# Power_Supply.net
KiCad netlist of a schematic drawn in Altium Designer
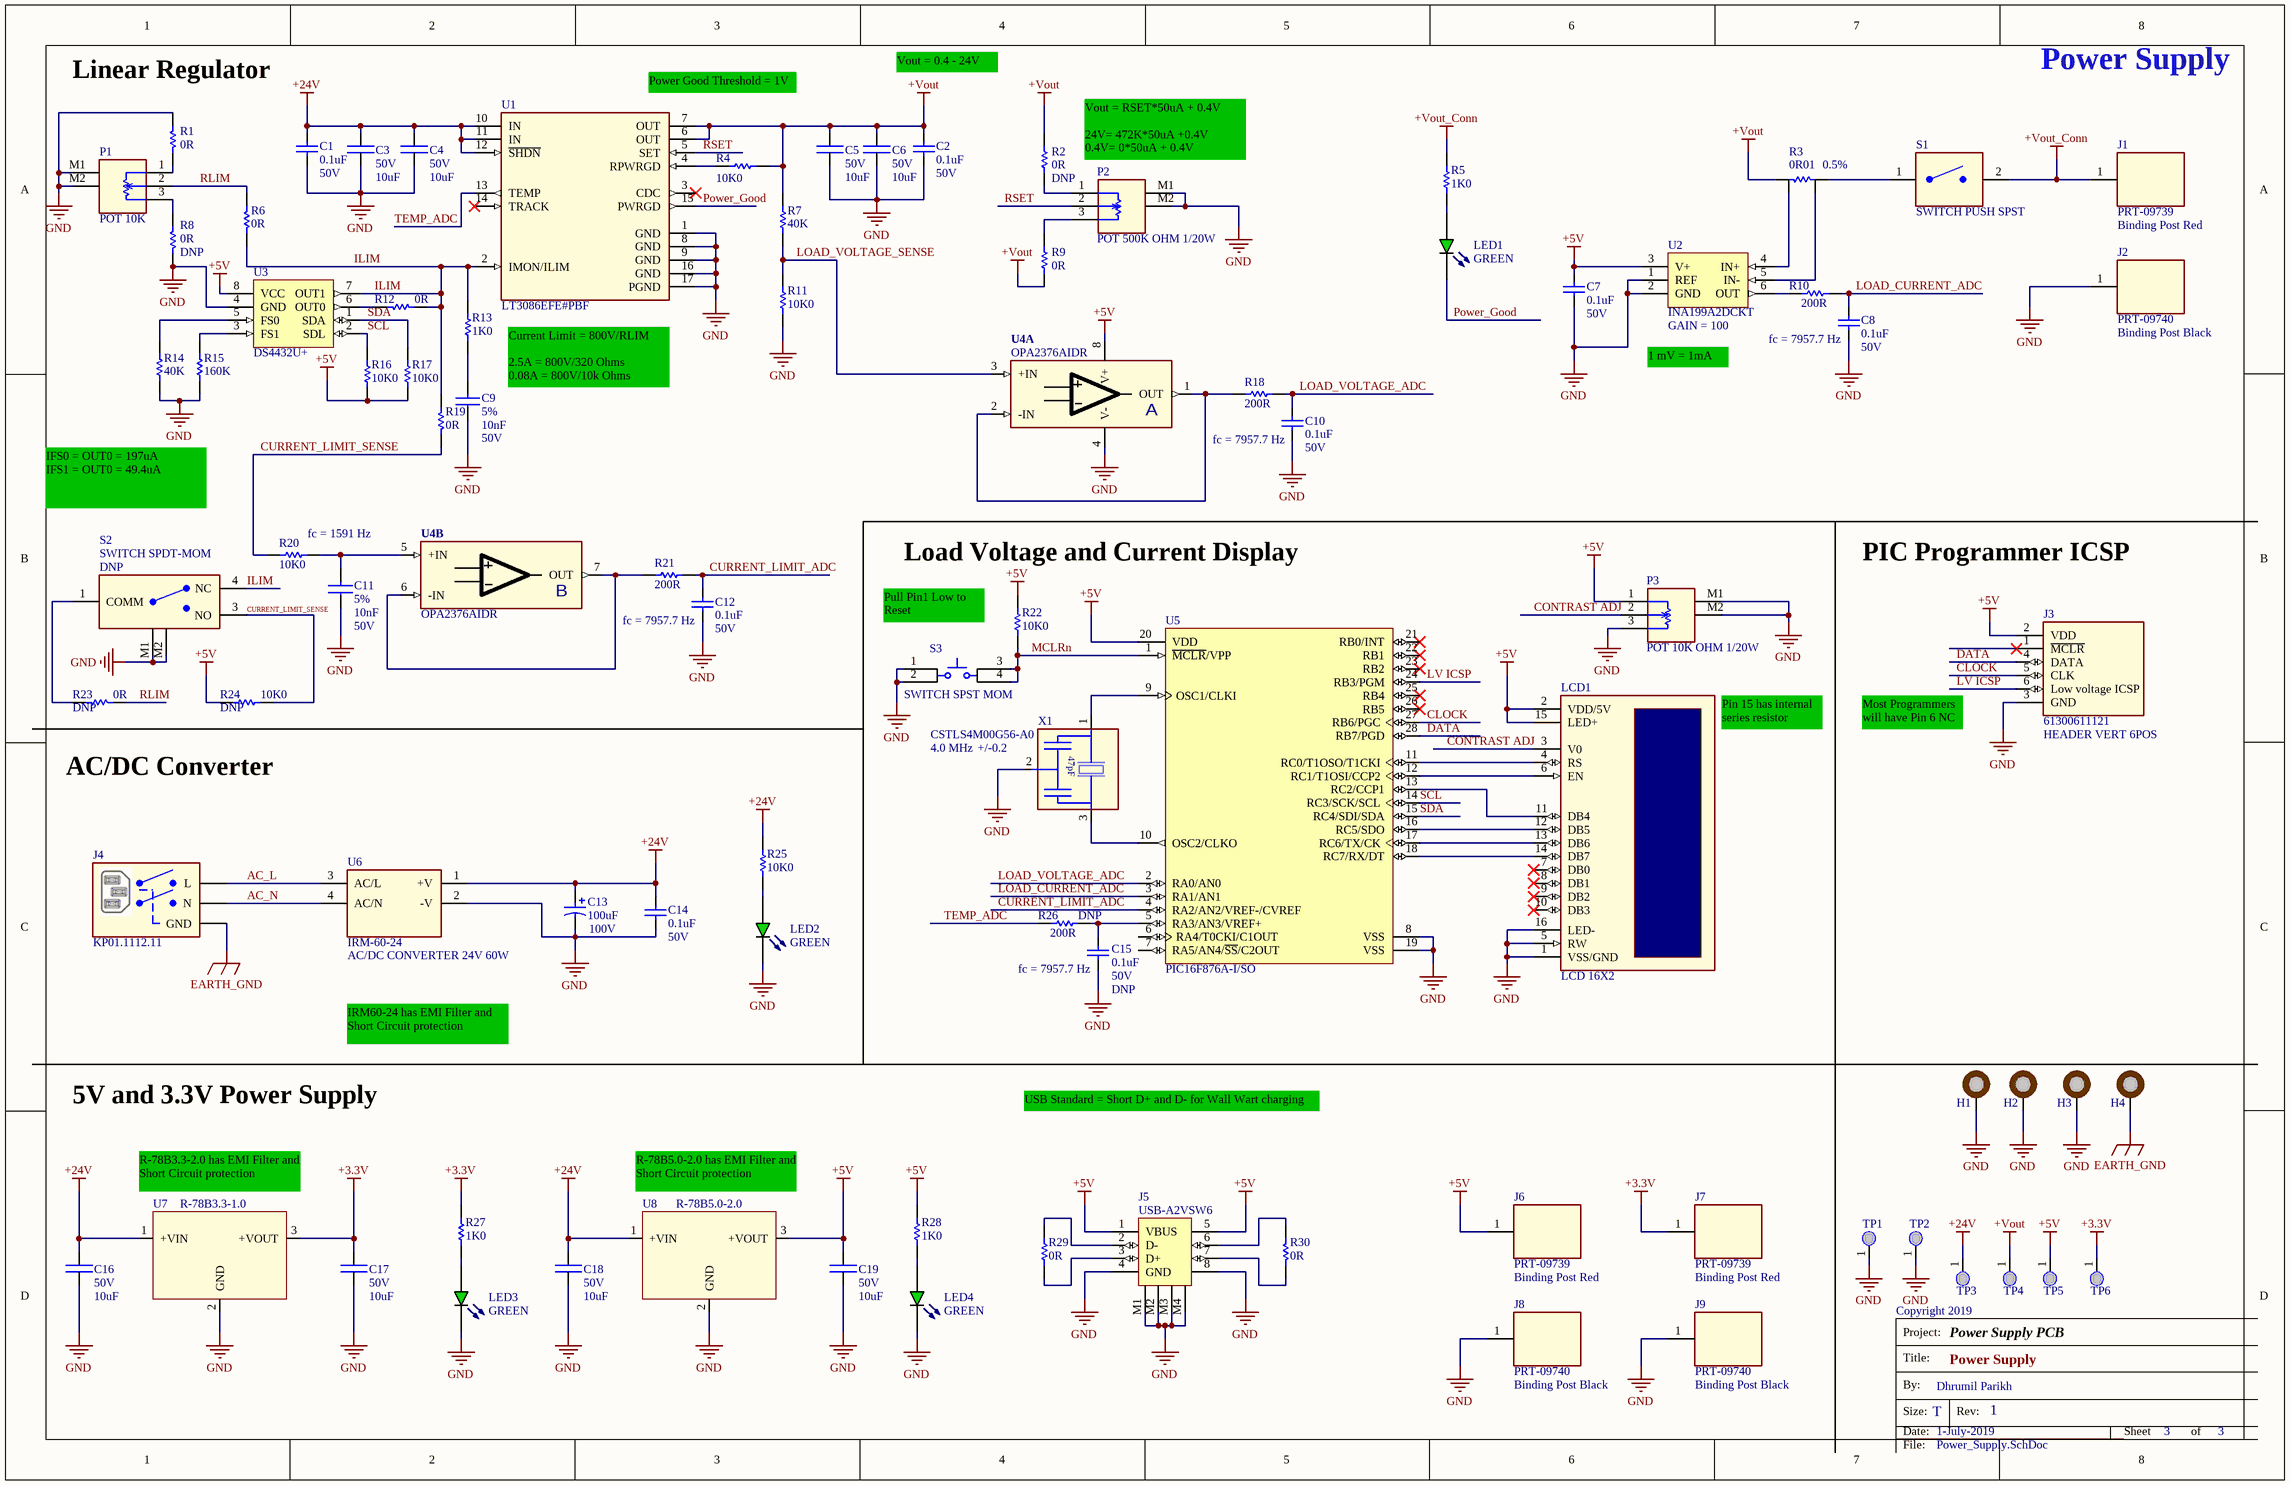
[diagram p0: Power_Supply.SchDoc]

(export (version "E")
  (design (tool "Eeschema 10.0.6"))
  (components
    (comp (ref "C1")
      (value "0.1uF")
      (footprint "CAPC1005X06N")
      (description "CAP CER 0.1UF 50V X7R 0402")
      (fields
        (field (name "MFG") "Taiyo Yuden")
        (field (name "MFG_PART_NO") "UMK105B7104KVHF")
        (field (name "VOLTAGE") "50V")
      )
      (libsource (lib "PowerSupply") (part "CAP CER 0.1UF 50V X7R 0402"))
    )
    (comp (ref "C2")
      (value "0.1uF")
      (footprint "CAPC1005X06N")
      (description "CAP CER 0.1UF 50V X7R 0402")
      (fields
        (field (name "MFG") "Taiyo Yuden")
        (field (name "MFG_PART_NO") "UMK105B7104KVHF")
        (field (name "VOLTAGE") "50V")
      )
      (libsource (lib "PowerSupply") (part "CAP CER 0.1UF 50V X7R 0402"))
    )
    (comp (ref "C3")
      (value "10uF")
      (footprint "CAPC3225X28N")
      (description "CAP CER 10UF 50V X7S 1210")
      (fields
        (field (name "MFG") "Taiyo Yuden")
        (field (name "MFG_PART_NO") "UMK325C7106MM-T")
        (field (name "VOLTAGE") "50V")
      )
      (libsource (lib "PowerSupply") (part "CAP CER 10UF 50V X7S 1210"))
    )
    (comp (ref "C4")
      (value "10uF")
      (footprint "CAPC3225X28N")
      (description "CAP CER 10UF 50V X7S 1210")
      (fields
        (field (name "MFG") "Taiyo Yuden")
        (field (name "MFG_PART_NO") "UMK325C7106MM-T")
        (field (name "VOLTAGE") "50V")
      )
      (libsource (lib "PowerSupply") (part "CAP CER 10UF 50V X7S 1210"))
    )
    (comp (ref "C5")
      (value "10uF")
      (footprint "CAPC3225X28N")
      (description "CAP CER 10UF 50V X7S 1210")
      (fields
        (field (name "MFG") "Taiyo Yuden")
        (field (name "MFG_PART_NO") "UMK325C7106MM-T")
        (field (name "VOLTAGE") "50V")
      )
      (libsource (lib "PowerSupply") (part "CAP CER 10UF 50V X7S 1210"))
    )
    (comp (ref "C6")
      (value "10uF")
      (footprint "CAPC3225X28N")
      (description "CAP CER 10UF 50V X7S 1210")
      (fields
        (field (name "MFG") "Taiyo Yuden")
        (field (name "MFG_PART_NO") "UMK325C7106MM-T")
        (field (name "VOLTAGE") "50V")
      )
      (libsource (lib "PowerSupply") (part "CAP CER 10UF 50V X7S 1210"))
    )
    (comp (ref "C7")
      (value "0.1uF")
      (footprint "CAPC1005X06N")
      (description "CAP CER 0.1UF 50V X7R 0402")
      (fields
        (field (name "MFG") "Taiyo Yuden")
        (field (name "MFG_PART_NO") "UMK105B7104KVHF")
        (field (name "VOLTAGE") "50V")
      )
      (libsource (lib "PowerSupply") (part "CAP CER 0.1UF 50V X7R 0402"))
    )
    (comp (ref "C8")
      (value "0.1uF")
      (footprint "CAPC1005X06N")
      (description "CAP CER 0.1UF 50V X7R 0402")
      (fields
        (field (name "MFG") "Taiyo Yuden")
        (field (name "MFG_PART_NO") "UMK105B7104KVHF")
        (field (name "VOLTAGE") "50V")
      )
      (libsource (lib "PowerSupply") (part "CAP CER 0.1UF 50V X7R 0402"))
    )
    (comp (ref "C9")
      (value "10nF")
      (footprint "CAPC1608X09N")
      (description "CAP CER 10000PF 50V 5% C0G 0603")
      (fields
        (field (name "MFG") "Murata")
        (field (name "MFG_PART_NO") "GRM1885C1H103JA01D")
        (field (name "TOLERANCE") "5%")
        (field (name "VOLTAGE") "50V")
      )
      (libsource (lib "PowerSupply") (part "CAP CER 10000PF 50V 5% C0G 0603"))
    )
    (comp (ref "C10")
      (value "0.1uF")
      (footprint "CAPC1005X06N")
      (description "CAP CER 0.1UF 50V X7R 0402")
      (fields
        (field (name "MFG") "Taiyo Yuden")
        (field (name "MFG_PART_NO") "UMK105B7104KVHF")
        (field (name "VOLTAGE") "50V")
      )
      (libsource (lib "PowerSupply") (part "CAP CER 0.1UF 50V X7R 0402"))
    )
    (comp (ref "C11")
      (value "10nF")
      (footprint "CAPC1608X09N")
      (description "CAP CER 10000PF 50V 5% C0G 0603")
      (fields
        (field (name "MFG") "Murata")
        (field (name "MFG_PART_NO") "GRM1885C1H103JA01D")
        (field (name "TOLERANCE") "5%")
        (field (name "VOLTAGE") "50V")
      )
      (libsource (lib "PowerSupply") (part "CAP CER 10000PF 50V 5% C0G 0603"))
    )
    (comp (ref "C12")
      (value "0.1uF")
      (footprint "CAPC1005X06N")
      (description "CAP CER 0.1UF 50V X7R 0402")
      (fields
        (field (name "MFG") "Taiyo Yuden")
        (field (name "MFG_PART_NO") "UMK105B7104KVHF")
        (field (name "VOLTAGE") "50V")
      )
      (libsource (lib "PowerSupply") (part "CAP CER 0.1UF 50V X7R 0402"))
    )
    (comp (ref "C13")
      (value "100uF")
      (footprint "CAPAE1300X1400N")
      (description "CAP ALUM 100UF 20% 100V SMD")
      (fields
        (field (name "MFG") "United Chemi-Con")
        (field (name "MFG_PART_NO") "EMVY101ARA101MKE0S")
        (field (name "VOLTAGE") "100V")
      )
      (libsource (lib "PowerSupply") (part "CAP ALUM 100UF 20% 100V SMD"))
    )
    (comp (ref "C14")
      (value "0.1uF")
      (footprint "CAPC1005X06N")
      (description "CAP CER 0.1UF 50V X7R 0402")
      (fields
        (field (name "MFG") "Taiyo Yuden")
        (field (name "MFG_PART_NO") "UMK105B7104KVHF")
        (field (name "VOLTAGE") "50V")
      )
      (libsource (lib "PowerSupply") (part "CAP CER 0.1UF 50V X7R 0402"))
    )
    (comp (ref "C15")
      (value "0.1uF")
      (footprint "CAPC1005X06N")
      (description "CAP CER 0.1UF 50V X7R 0402")
      (fields
        (field (name "MFG") "Taiyo Yuden")
        (field (name "NOSTUFF") "DNP")
        (field (name "MFG_PART_NO") "UMK105B7104KVHF")
        (field (name "VOLTAGE") "50V")
      )
      (libsource (lib "PowerSupply") (part "CAP CER 0.1UF 50V X7R 0402"))
    )
    (comp (ref "C16")
      (value "10uF")
      (footprint "CAPC3225X28N")
      (description "CAP CER 10UF 50V X7S 1210")
      (fields
        (field (name "MFG") "Taiyo Yuden")
        (field (name "MFG_PART_NO") "UMK325C7106MM-T")
        (field (name "VOLTAGE") "50V")
      )
      (libsource (lib "PowerSupply") (part "CAP CER 10UF 50V X7S 1210"))
    )
    (comp (ref "C17")
      (value "10uF")
      (footprint "CAPC3225X28N")
      (description "CAP CER 10UF 50V X7S 1210")
      (fields
        (field (name "MFG") "Taiyo Yuden")
        (field (name "MFG_PART_NO") "UMK325C7106MM-T")
        (field (name "VOLTAGE") "50V")
      )
      (libsource (lib "PowerSupply") (part "CAP CER 10UF 50V X7S 1210"))
    )
    (comp (ref "C18")
      (value "10uF")
      (footprint "CAPC3225X28N")
      (description "CAP CER 10UF 50V X7S 1210")
      (fields
        (field (name "MFG") "Taiyo Yuden")
        (field (name "MFG_PART_NO") "UMK325C7106MM-T")
        (field (name "VOLTAGE") "50V")
      )
      (libsource (lib "PowerSupply") (part "CAP CER 10UF 50V X7S 1210"))
    )
    (comp (ref "C19")
      (value "10uF")
      (footprint "CAPC3225X28N")
      (description "CAP CER 10UF 50V X7S 1210")
      (fields
        (field (name "MFG") "Taiyo Yuden")
        (field (name "MFG_PART_NO") "UMK325C7106MM-T")
        (field (name "VOLTAGE") "50V")
      )
      (libsource (lib "PowerSupply") (part "CAP CER 10UF 50V X7S 1210"))
    )
    (comp (ref "H1")
      (value "MTG_HOLE PTH, 3.0mm")
      (footprint "MH_PTH_H3.0mmXP6.0mm")
      (description "PTH, 3.0mm")
      (libsource (lib "PowerSupply") (part "MTG_HOLE PTH, 3.0mm"))
    )
    (comp (ref "H2")
      (value "MTG_HOLE PTH, 3.0mm")
      (footprint "MH_PTH_H3.0mmXP6.0mm")
      (description "PTH, 3.0mm")
      (libsource (lib "PowerSupply") (part "MTG_HOLE PTH, 3.0mm"))
    )
    (comp (ref "H3")
      (value "MTG_HOLE PTH, 3.0mm")
      (footprint "MH_PTH_H3.0mmXP6.0mm")
      (description "PTH, 3.0mm")
      (libsource (lib "PowerSupply") (part "MTG_HOLE PTH, 3.0mm"))
    )
    (comp (ref "H4")
      (value "MTG_HOLE PTH, 3.0mm")
      (footprint "MH_PTH_H3.0mmXP6.0mm")
      (description "PTH, 3.0mm")
      (libsource (lib "PowerSupply") (part "MTG_HOLE PTH, 3.0mm"))
    )
    (comp (ref "J1")
      (value "Binding Post Red")
      (footprint "PRT-09739")
      (description "CONN BIND POST KNURLED RED")
      (fields (field (name "MFG") "SparkFun Electronics") (field (name "MFG_PART_NO") "PRT-09739"))
      (libsource (lib "PowerSupply") (part "CONN BIND POST KNURLED RED"))
    )
    (comp (ref "J2")
      (value "Binding Post Black")
      (footprint "PRT-09740")
      (description "CONN BIND POST KNURLED BLACK")
      (fields (field (name "MFG") "SparkFun Electronics") (field (name "MFG_PART_NO") "PRT-09740"))
      (libsource (lib "PowerSupply") (part "CONN BIND POST KNURLED BLACK"))
    )
    (comp (ref "J3")
      (value "HEADER VERT 6POS")
      (footprint "61300611121")
      (description "CONN HEADER VERT 6POS 2.54MM")
      (fields (field (name "MFG") "Wurth Electronics Inc.") (field (name "MFG_PART_NO") "61300611121"))
      (libsource (lib "PowerSupply") (part "CONN HEADER VERT 6POS 2.54MM"))
    )
    (comp (ref "J4")
      (value "PWR ENT MOD RCPT IEC320-C14 PNL")
      (footprint "KP01.1112.11")
      (fields (field (name "MFG") "Schurter Inc.") (field (name "MFG_PART_NO") "KP01.1112.11"))
      (libsource (lib "PowerSupply") (part "PWR ENT MOD RCPT IEC320-C14 PNL"))
    )
    (comp (ref "J5")
      (value "USB-A2VSW6")
      (footprint "USB-A2VSW6")
      (description "CONN RCPT TYPEA STACK 8POS VERT")
      (fields (field (name "MFG") "On Shore Technology Inc."))
      (libsource (lib "PowerSupply") (part "CONN RCPT TYPEA STACK 8POS VERT"))
    )
    (comp (ref "J6")
      (value "Binding Post Red")
      (footprint "PRT-09739")
      (description "CONN BIND POST KNURLED RED")
      (fields (field (name "MFG") "SparkFun Electronics") (field (name "MFG_PART_NO") "PRT-09739"))
      (libsource (lib "PowerSupply") (part "CONN BIND POST KNURLED RED"))
    )
    (comp (ref "J7")
      (value "Binding Post Red")
      (footprint "PRT-09739")
      (description "CONN BIND POST KNURLED RED")
      (fields (field (name "MFG") "SparkFun Electronics") (field (name "MFG_PART_NO") "PRT-09739"))
      (libsource (lib "PowerSupply") (part "CONN BIND POST KNURLED RED"))
    )
    (comp (ref "J8")
      (value "Binding Post Black")
      (footprint "PRT-09740")
      (description "CONN BIND POST KNURLED BLACK")
      (fields (field (name "MFG") "SparkFun Electronics") (field (name "MFG_PART_NO") "PRT-09740"))
      (libsource (lib "PowerSupply") (part "CONN BIND POST KNURLED BLACK"))
    )
    (comp (ref "J9")
      (value "Binding Post Black")
      (footprint "PRT-09740")
      (description "CONN BIND POST KNURLED BLACK")
      (fields (field (name "MFG") "SparkFun Electronics") (field (name "MFG_PART_NO") "PRT-09740"))
      (libsource (lib "PowerSupply") (part "CONN BIND POST KNURLED BLACK"))
    )
    (comp (ref "LCD1")
      (value "LCD 16X2")
      (footprint "LCD_16pin")
      (description "STANDARD LCD 16X2 + EXTRAS")
      (fields (field (name "MFG") "Adafruit Industries LLC") (field (name "MFG_PART_NO") "181"))
      (libsource (lib "PowerSupply") (part "STANDARD LCD 16X2 + EXTRAS"))
    )
    (comp (ref "LED1")
      (value "GREEN")
      (footprint "LED LTST-C190KGKT")
      (description "LED SUPER GREEN CLEAR 0603 SMD")
      (fields (field (name "MFG") "Lite-On") (field (name "MFG_PART_NO") "0.39"))
      (libsource (lib "PowerSupply") (part "LED GREEN"))
    )
    (comp (ref "LED2")
      (value "GREEN")
      (footprint "LED LTST-C190KGKT")
      (description "LED SUPER GREEN CLEAR 0603 SMD")
      (fields (field (name "MFG") "Lite-On") (field (name "MFG_PART_NO") "0.39"))
      (libsource (lib "PowerSupply") (part "LED GREEN"))
    )
    (comp (ref "LED3")
      (value "GREEN")
      (footprint "LED LTST-C190KGKT")
      (description "LED SUPER GREEN CLEAR 0603 SMD")
      (fields (field (name "MFG") "Lite-On") (field (name "MFG_PART_NO") "0.39"))
      (libsource (lib "PowerSupply") (part "LED GREEN"))
    )
    (comp (ref "LED4")
      (value "GREEN")
      (footprint "LED LTST-C190KGKT")
      (description "LED SUPER GREEN CLEAR 0603 SMD")
      (fields (field (name "MFG") "Lite-On") (field (name "MFG_PART_NO") "0.39"))
      (libsource (lib "PowerSupply") (part "LED GREEN"))
    )
    (comp (ref "P1")
      (value "POT 10K")
      (footprint "PTV09A")
      (description "POT 10K OHM 1/20W CARBON LOG")
      (fields (field (name "MFG") "Bourns Inc.") (field (name "MFG_PART_NO") "PTV09A-4020F-A103"))
      (libsource (lib "") (part "POT 10K OHM 1/20W CARBON LOG_1"))
    )
    (comp (ref "P2")
      (value "POT 500K OHM 1/20W")
      (footprint "PTV09A")
      (description "POT 500K OHM 1/20W CARBON LOG")
      (fields (field (name "MFG") "Bourns Inc.") (field (name "MFG_PART_NO") "PTV09A-4020F-A504"))
      (libsource (lib "PowerSupply") (part "POT 500K OHM 1/20W CARBON LOG"))
    )
    (comp (ref "P3")
      (value "POT 10K OHM 1/20W")
      (footprint "PTV09A")
      (description "POT 10K OHM 1/20W CARBON LOG")
      (fields (field (name "MFG") "Bourns Inc.") (field (name "MFG_PART_NO") "PTV09A-4020F-A103"))
      (libsource (lib "PowerSupply") (part "POT 10K OHM 1/20W CARBON LOG"))
    )
    (comp (ref "R1")
      (value "0R")
      (footprint "RESC2012X07N")
      (description "RES SMD 0 OHM JUMPER 1/8W 0805")
      (fields (field (name "MFG") "Panasonic") (field (name "MFG_PART_NO") "ERJ-6GEY0R00V"))
      (libsource (lib "PowerSupply") (part "RES SMD 0 OHM JUMPER 1/8W 0805"))
    )
    (comp (ref "R2")
      (value "0R")
      (footprint "RESC2012X07N")
      (description "RES SMD 0 OHM JUMPER 1/8W 0805")
      (fields
        (field (name "MFG") "Panasonic")
        (field (name "NOSTUFF") "DNP")
        (field (name "MFG_PART_NO") "ERJ-6GEY0R00V")
      )
      (libsource (lib "PowerSupply") (part "RES SMD 0 OHM JUMPER 1/8W 0805"))
    )
    (comp (ref "R3")
      (value "0R01")
      (footprint "FC4TR010DER")
      (description "RES 0.01 OHM 0.5% 1/2W 1206 WIDE")
      (fields
        (field (name "MFG") "Ohmite")
        (field (name "MFG_PART_NO") "FC4TR010DER")
        (field (name "TOLERANCE") "0.5%")
      )
      (libsource (lib "PowerSupply") (part "RES 0.01 OHM 0.5% 1/2W 1206 WIDE"))
    )
    (comp (ref "R4")
      (value "10K0")
      (footprint "RESC1608X06N")
      (description "RES SMD 10K OHM 1% 1/4W 0603")
      (fields (field (name "MFG") "Rohm") (field (name "MFG_PART_NO") "ESR03EZPF1002"))
      (libsource (lib "PowerSupply") (part "RES SMD 10K OHM 1% 1/4W 0603"))
    )
    (comp (ref "R5")
      (value "1K0")
      (footprint "RESC1608X06N")
      (description "RES SMD 1K OHM 1% 1/10W 0603")
      (fields (field (name "MFG") "Stackpole") (field (name "MFG_PART_NO") "RMCF0603FT1K00"))
      (libsource (lib "PowerSupply") (part "RES SMD 1K OHM 1% 1/10W 0603"))
    )
    (comp (ref "R6")
      (value "0R")
      (footprint "RESC2012X07N")
      (description "RES SMD 0 OHM JUMPER 1/8W 0805")
      (fields (field (name "MFG") "Panasonic") (field (name "MFG_PART_NO") "ERJ-6GEY0R00V"))
      (libsource (lib "PowerSupply") (part "RES SMD 0 OHM JUMPER 1/8W 0805"))
    )
    (comp (ref "R7")
      (value "40K")
      (footprint "RESC1608X06N")
      (description "RES SMD 40K OHM 0.1% 0.15W 0603")
      (fields (field (name "MFG") "Vishay Thin Film") (field (name "MFG_PART_NO") "PAT0603E4002BST1"))
      (libsource (lib "PowerSupply") (part "RES SMD 40K OHM 0.1% 0.15W 0603"))
    )
    (comp (ref "R8")
      (value "0R")
      (footprint "RESC2012X07N")
      (description "RES SMD 0 OHM JUMPER 1/8W 0805")
      (fields
        (field (name "MFG") "Panasonic")
        (field (name "NOSTUFF") "DNP")
        (field (name "MFG_PART_NO") "ERJ-6GEY0R00V")
      )
      (libsource (lib "PowerSupply") (part "RES SMD 0 OHM JUMPER 1/8W 0805"))
    )
    (comp (ref "R9")
      (value "0R")
      (footprint "RESC2012X07N")
      (description "RES SMD 0 OHM JUMPER 1/8W 0805")
      (fields (field (name "MFG") "Panasonic") (field (name "MFG_PART_NO") "ERJ-6GEY0R00V"))
      (libsource (lib "PowerSupply") (part "RES SMD 0 OHM JUMPER 1/8W 0805"))
    )
    (comp (ref "R10")
      (value "200R")
      (footprint "RESC1608X06N")
      (description "RES SMD 200 OHM 1% 1/10W 0603")
      (fields (field (name "MFG") "Yageo") (field (name "POWER") "0.1W"))
      (libsource (lib "PowerSupply") (part "RES SMD 200 OHM 1% 1/10W 0603"))
    )
    (comp (ref "R11")
      (value "10K0")
      (footprint "RESC1608X06N")
      (description "RES SMD 10K OHM 1% 1/4W 0603")
      (fields (field (name "MFG") "Rohm") (field (name "MFG_PART_NO") "ESR03EZPF1002"))
      (libsource (lib "PowerSupply") (part "RES SMD 10K OHM 1% 1/4W 0603"))
    )
    (comp (ref "R12")
      (value "0R")
      (footprint "RESC2012X07N")
      (description "RES SMD 0 OHM JUMPER 1/8W 0805")
      (fields (field (name "MFG") "Panasonic") (field (name "MFG_PART_NO") "ERJ-6GEY0R00V"))
      (libsource (lib "PowerSupply") (part "RES SMD 0 OHM JUMPER 1/8W 0805"))
    )
    (comp (ref "R13")
      (value "1K0")
      (footprint "RESC1608X06N")
      (description "RES SMD 1K OHM 1% 1/10W 0603")
      (fields (field (name "MFG") "Stackpole") (field (name "MFG_PART_NO") "RMCF0603FT1K00"))
      (libsource (lib "PowerSupply") (part "RES SMD 1K OHM 1% 1/10W 0603"))
    )
    (comp (ref "R14")
      (value "40K")
      (footprint "RESC1608X06N")
      (description "RES SMD 40K OHM 0.1% 0.15W 0603")
      (fields (field (name "MFG") "Vishay Thin Film") (field (name "MFG_PART_NO") "PAT0603E4002BST1"))
      (libsource (lib "PowerSupply") (part "RES SMD 40K OHM 0.1% 0.15W 0603"))
    )
    (comp (ref "R15")
      (value "160K")
      (footprint "RESC1608X06N")
      (description "RES SMD 160K OHM 1% 1/10W 0603")
      (fields (field (name "MFG") "Yageo") (field (name "MFG_PART_NO") "RC0603FR-07160KL"))
      (libsource (lib "PowerSupply") (part "RES SMD 160K OHM 1% 1/10W 0603"))
    )
    (comp (ref "R16")
      (value "10K0")
      (footprint "RESC1608X06N")
      (description "RES SMD 10K OHM 1% 1/4W 0603")
      (fields (field (name "MFG") "Rohm") (field (name "MFG_PART_NO") "ESR03EZPF1002"))
      (libsource (lib "PowerSupply") (part "RES SMD 10K OHM 1% 1/4W 0603"))
    )
    (comp (ref "R17")
      (value "10K0")
      (footprint "RESC1608X06N")
      (description "RES SMD 10K OHM 1% 1/4W 0603")
      (fields (field (name "MFG") "Rohm") (field (name "MFG_PART_NO") "ESR03EZPF1002"))
      (libsource (lib "PowerSupply") (part "RES SMD 10K OHM 1% 1/4W 0603"))
    )
    (comp (ref "R18")
      (value "200R")
      (footprint "RESC1608X06N")
      (description "RES SMD 200 OHM 1% 1/10W 0603")
      (fields (field (name "MFG") "Yageo") (field (name "POWER") "0.1W"))
      (libsource (lib "PowerSupply") (part "RES SMD 200 OHM 1% 1/10W 0603"))
    )
    (comp (ref "R19")
      (value "0R")
      (footprint "RESC2012X07N")
      (description "RES SMD 0 OHM JUMPER 1/8W 0805")
      (fields (field (name "MFG") "Panasonic") (field (name "MFG_PART_NO") "ERJ-6GEY0R00V"))
      (libsource (lib "PowerSupply") (part "RES SMD 0 OHM JUMPER 1/8W 0805"))
    )
    (comp (ref "R20")
      (value "10K0")
      (footprint "RESC1608X06N")
      (description "RES SMD 10K OHM 1% 1/4W 0603")
      (fields (field (name "MFG") "Rohm") (field (name "MFG_PART_NO") "ESR03EZPF1002"))
      (libsource (lib "PowerSupply") (part "RES SMD 10K OHM 1% 1/4W 0603"))
    )
    (comp (ref "R21")
      (value "200R")
      (footprint "RESC1608X06N")
      (description "RES SMD 200 OHM 1% 1/10W 0603")
      (fields (field (name "MFG") "Yageo") (field (name "POWER") "0.1W"))
      (libsource (lib "PowerSupply") (part "RES SMD 200 OHM 1% 1/10W 0603"))
    )
    (comp (ref "R22")
      (value "10K0")
      (footprint "RESC1608X06N")
      (description "RES SMD 10K OHM 1% 1/4W 0603")
      (fields (field (name "MFG") "Rohm") (field (name "MFG_PART_NO") "ESR03EZPF1002"))
      (libsource (lib "PowerSupply") (part "RES SMD 10K OHM 1% 1/4W 0603"))
    )
    (comp (ref "R23")
      (value "0R")
      (footprint "RESC2012X07N")
      (description "RES SMD 0 OHM JUMPER 1/8W 0805")
      (fields
        (field (name "MFG") "Panasonic")
        (field (name "NOSTUFF") "DNP")
        (field (name "MFG_PART_NO") "ERJ-6GEY0R00V")
      )
      (libsource (lib "PowerSupply") (part "RES SMD 0 OHM JUMPER 1/8W 0805"))
    )
    (comp (ref "R24")
      (value "10K0")
      (footprint "RESC1608X06N")
      (description "RES SMD 10K OHM 1% 1/4W 0603")
      (fields
        (field (name "MFG") "Rohm")
        (field (name "NOSTUFF") "DNP")
        (field (name "MFG_PART_NO") "ESR03EZPF1002")
      )
      (libsource (lib "PowerSupply") (part "RES SMD 10K OHM 1% 1/4W 0603"))
    )
    (comp (ref "R25")
      (value "10K0")
      (footprint "RESC1608X06N")
      (description "RES SMD 10K OHM 1% 1/4W 0603")
      (fields (field (name "MFG") "Rohm") (field (name "MFG_PART_NO") "ESR03EZPF1002"))
      (libsource (lib "PowerSupply") (part "RES SMD 10K OHM 1% 1/4W 0603"))
    )
    (comp (ref "R26")
      (value "200R")
      (footprint "RESC1608X06N")
      (description "RES SMD 200 OHM 1% 1/10W 0603")
      (fields (field (name "MFG") "Yageo") (field (name "NOSTUFF") "DNP") (field (name "POWER") "0.1W"))
      (libsource (lib "PowerSupply") (part "RES SMD 200 OHM 1% 1/10W 0603"))
    )
    (comp (ref "R27")
      (value "1K0")
      (footprint "RESC1608X06N")
      (description "RES SMD 1K OHM 1% 1/10W 0603")
      (fields (field (name "MFG") "Stackpole") (field (name "MFG_PART_NO") "RMCF0603FT1K00"))
      (libsource (lib "PowerSupply") (part "RES SMD 1K OHM 1% 1/10W 0603"))
    )
    (comp (ref "R28")
      (value "1K0")
      (footprint "RESC1608X06N")
      (description "RES SMD 1K OHM 1% 1/10W 0603")
      (fields (field (name "MFG") "Stackpole") (field (name "MFG_PART_NO") "RMCF0603FT1K00"))
      (libsource (lib "PowerSupply") (part "RES SMD 1K OHM 1% 1/10W 0603"))
    )
    (comp (ref "R29")
      (value "0R")
      (footprint "RESC2012X07N")
      (description "RES SMD 0 OHM JUMPER 1/8W 0805")
      (fields (field (name "MFG") "Panasonic") (field (name "MFG_PART_NO") "ERJ-6GEY0R00V"))
      (libsource (lib "PowerSupply") (part "RES SMD 0 OHM JUMPER 1/8W 0805"))
    )
    (comp (ref "R30")
      (value "0R")
      (footprint "RESC2012X07N")
      (description "RES SMD 0 OHM JUMPER 1/8W 0805")
      (fields (field (name "MFG") "Panasonic") (field (name "MFG_PART_NO") "ERJ-6GEY0R00V"))
      (libsource (lib "PowerSupply") (part "RES SMD 0 OHM JUMPER 1/8W 0805"))
    )
    (comp (ref "S1")
      (value "SWITCH PUSH SPST")
      (footprint "PB1973ABLKBLKEF0")
      (description "SWITCH PUSH SPST 15A 250V")
      (fields (field (name "MFG") "E-Switch") (field (name "MFG_PART_NO") "PB1973ABLKBLKEF0"))
      (libsource (lib "PowerSupply") (part "SWITCH PUSH SPST 15A 250V"))
    )
    (comp (ref "S2")
      (value "SWITCH SPDT-MOM")
      (footprint "KS12R22CQD")
      (description "SWITCH PUSH SPDT 0.025A 50V")
      (fields
        (field (name "MFG") "C&K")
        (field (name "NOSTUFF") "DNP")
        (field (name "MFG_PART_NO") "KS12R22CQD")
      )
      (libsource (lib "PowerSupply") (part "SWITCH PUSH SPDT 0.025A 50V"))
    )
    (comp (ref "S3")
      (value "SWITCH SPST MOM")
      (footprint "PTS645SM43SMTR92LFS")
      (description "SWITCH TACTILE SPST-NO 0.05A 12V")
      (fields (field (name "MFG") "C&K") (field (name "VOLTAGE") "12V"))
      (libsource (lib "PowerSupply") (part "SWITCH TACTILE SPST-NO 0.05A 12V"))
    )
    (comp (ref "TP1")
      (value "Testpoint Harwin S2751-46R")
      (footprint "TP_HARWIN_2751-46R")
      (description "PC TEST POINT TIN SMD")
      (fields (field (name "MFG") "Harwin Inc.") (field (name "MFG_PART_NO") "S2751-46R"))
      (libsource (lib "PowerSupply") (part "Testpoint Harwin S2751-46R"))
    )
    (comp (ref "TP2")
      (value "Testpoint Harwin S2751-46R")
      (footprint "TP_HARWIN_2751-46R")
      (description "PC TEST POINT TIN SMD")
      (fields (field (name "MFG") "Harwin Inc.") (field (name "MFG_PART_NO") "S2751-46R"))
      (libsource (lib "PowerSupply") (part "Testpoint Harwin S2751-46R"))
    )
    (comp (ref "TP3")
      (value "Testpoint Harwin S2751-46R")
      (footprint "TP_HARWIN_2751-46R")
      (description "PC TEST POINT TIN SMD")
      (fields (field (name "MFG") "Harwin Inc.") (field (name "MFG_PART_NO") "S2751-46R"))
      (libsource (lib "PowerSupply") (part "Testpoint Harwin S2751-46R"))
    )
    (comp (ref "TP4")
      (value "Testpoint Harwin S2751-46R")
      (footprint "TP_HARWIN_2751-46R")
      (description "PC TEST POINT TIN SMD")
      (fields (field (name "MFG") "Harwin Inc.") (field (name "MFG_PART_NO") "S2751-46R"))
      (libsource (lib "PowerSupply") (part "Testpoint Harwin S2751-46R"))
    )
    (comp (ref "TP5")
      (value "Testpoint Harwin S2751-46R")
      (footprint "TP_HARWIN_2751-46R")
      (description "PC TEST POINT TIN SMD")
      (fields (field (name "MFG") "Harwin Inc.") (field (name "MFG_PART_NO") "S2751-46R"))
      (libsource (lib "PowerSupply") (part "Testpoint Harwin S2751-46R"))
    )
    (comp (ref "TP6")
      (value "Testpoint Harwin S2751-46R")
      (footprint "TP_HARWIN_2751-46R")
      (description "PC TEST POINT TIN SMD")
      (fields (field (name "MFG") "Harwin Inc.") (field (name "MFG_PART_NO") "S2751-46R"))
      (libsource (lib "PowerSupply") (part "Testpoint Harwin S2751-46R"))
    )
    (comp (ref "U1")
      (value "LT3086EFE#PBF")
      (footprint "TSOP65P640X110_HS-17N")
      (description "IC REG LIN POS ADJ 2.1A 16TSSOP")
      (fields (field (name "MFG") "Linear Technology/Analog Devices"))
      (libsource (lib "PowerSupply") (part "IC REG LIN POS ADJ 2.1A 16TSSOP"))
    )
    (comp (ref "U2")
      (value "INA199A2DCKT")
      (footprint "TSOP65P240X110-6N")
      (description "IC OPAMP CURR SENSE 14KHZ SC70-6")
      (fields (field (name "MFG") "TE Connectivity AMP Connectors") (field (name "GAIN") "GAIN = 100"))
      (libsource (lib "PowerSupply") (part "IC OPAMP CURR SENSE 14KHZ SC70-6"))
    )
    (comp (ref "U3")
      (value "DS4432U+")
      (footprint "TSOP65P490X110-8N")
      (description "IC DAC 7BIT A-OUT 8UMAX")
      (fields (field (name "MFG") "Maxim Integrated"))
      (libsource (lib "PowerSupply") (part "IC DAC 7BIT A-OUT 8UMAX"))
    )
    (comp (ref "U4")
      (value "OPA2376AIDR")
      (footprint "SOIC127P600X175-8N_OPA2376AIDR")
      (description "IC OPAMP GP 5.5MHZ RRO 8SOIC")
      (fields (field (name "MFG") "TI") (field (name "Comment") "IC OPA2376AIDR"))
      (libsource (lib "PowerSupply") (part "IC OPA2376AIDR"))
    )
    (comp (ref "U5")
      (value "PIC16F876A-I/SO")
      (footprint "SOIC127P1030X264-28N")
      (description "IC MCU 8BIT 14KB FLASH 28SOIC")
      (fields (field (name "MFG") "Microchip Technology"))
      (libsource (lib "PowerSupply") (part "IC MCU 8BIT 14KB FLASH 28SOIC"))
    )
    (comp (ref "U6")
      (value "AC/DC CONVERTER 24V 60W")
      (footprint "IRM6024")
      (fields (field (name "MFG") "MEAN WELL USA Inc.") (field (name "MFG_PART_NO") "IRM-60-24"))
      (libsource (lib "PowerSupply") (part "AC/DC CONVERTER 24V 60W"))
    )
    (comp (ref "U7")
      (value "DC DC CONVERTER 3.3V 3W")
      (footprint "DC_Module_TH_R-78Bxx-1.0")
      (fields (field (name "MFG") "Recom Power") (field (name "MFG_PART_NO") "R-78B3.3-1.0"))
      (libsource (lib "PowerSupply") (part "DC DC CONVERTER 3.3V 3W"))
    )
    (comp (ref "U8")
      (value "DC DC CONVERTER 5V 10W")
      (footprint "DC_Module_TH_R-78Bxx-1.0")
      (fields (field (name "MFG") "Recom Power") (field (name "MFG_PART_NO") "R-78B5.0-2.0"))
      (libsource (lib "PowerSupply") (part "DC DC CONVERTER 5V 10W"))
    )
    (comp (ref "X1")
      (value "4.0 MHz")
      (footprint "CSTLS4M00G56-A0")
      (description "CER RESONATOR")
      (fields
        (field (name "TOLERANCE") "+/-0.5")
        (field (name "MFG_PART_NO") "CSTLS4M00G56-A0")
        (field (name "STABILITY") "+/-0.2")
      )
      (libsource (lib "PowerSupply") (part "CER RESONATOR"))
    )
  )
  (nets
    (net (code "1") (name "+3.3V") (class "Default")
      (node (ref "C17") (pin "1") (pinfunction "1_1") (pintype "passive"))
      (node (ref "J7") (pin "1") (pintype "power_in"))
      (node (ref "R27") (pin "2") (pinfunction "2_2") (pintype "passive"))
      (node (ref "TP6") (pin "1") (pinfunction "1_1") (pintype "passive"))
      (node (ref "U7") (pin "3") (pinfunction "+VOUT_3") (pintype "power_in"))
    )
    (net (code "2") (name "+5V") (class "Default")
      (node (ref "C19") (pin "1") (pinfunction "1_1") (pintype "passive"))
      (node (ref "C7") (pin "1") (pinfunction "1_1") (pintype "passive"))
      (node (ref "J3") (pin "2") (pinfunction "VDD_2") (pintype "power_in"))
      (node (ref "J5") (pin "1") (pinfunction "VBUS_1") (pintype "power_in"))
      (node (ref "J5") (pin "5") (pinfunction "VBUS_5") (pintype "power_in"))
      (node (ref "J6") (pin "1") (pintype "power_in"))
      (node (ref "LCD1") (pin "15") (pinfunction "LED+_15") (pintype "power_in"))
      (node (ref "LCD1") (pin "2") (pinfunction "VDD/5V_2") (pintype "power_in"))
      (node (ref "P3") (pin "1") (pintype "passive"))
      (node (ref "R16") (pin "1") (pinfunction "1_1") (pintype "passive"))
      (node (ref "R17") (pin "1") (pinfunction "1_1") (pintype "passive"))
      (node (ref "R22") (pin "2") (pinfunction "2_2") (pintype "passive"))
      (node (ref "R24") (pin "2") (pinfunction "2_2") (pintype "passive"))
      (node (ref "R28") (pin "2") (pinfunction "2_2") (pintype "passive"))
      (node (ref "TP5") (pin "1") (pinfunction "1_1") (pintype "passive"))
      (node (ref "U2") (pin "3") (pinfunction "V+_3") (pintype "power_in"))
      (node (ref "U3") (pin "8") (pinfunction "VCC_8") (pintype "power_in"))
      (node (ref "U4") (pin "8") (pinfunction "V+_8") (pintype "power_in"))
      (node (ref "U5") (pin "20") (pinfunction "VDD_20") (pintype "power_in"))
      (node (ref "U8") (pin "3") (pinfunction "+VOUT_3") (pintype "power_in"))
    )
    (net (code "3") (name "+24V") (class "Default")
      (node (ref "C1") (pin "1") (pinfunction "1_1") (pintype "passive"))
      (node (ref "C13") (pin "1") (pinfunction "1_1") (pintype "passive"))
      (node (ref "C14") (pin "1") (pinfunction "1_1") (pintype "passive"))
      (node (ref "C16") (pin "1") (pinfunction "1_1") (pintype "passive"))
      (node (ref "C18") (pin "1") (pinfunction "1_1") (pintype "passive"))
      (node (ref "C3") (pin "1") (pinfunction "1_1") (pintype "passive"))
      (node (ref "C4") (pin "1") (pinfunction "1_1") (pintype "passive"))
      (node (ref "R25") (pin "2") (pinfunction "2_2") (pintype "passive"))
      (node (ref "TP3") (pin "1") (pinfunction "1_1") (pintype "passive"))
      (node (ref "U1") (pin "10") (pinfunction "IN_10") (pintype "power_in"))
      (node (ref "U1") (pin "11") (pinfunction "IN_11") (pintype "power_in"))
      (node (ref "U1") (pin "12") (pinfunction "~{SHDN}_12") (pintype "input"))
      (node (ref "U6") (pin "1") (pinfunction "+V_1") (pintype "power_in"))
      (node (ref "U7") (pin "1") (pinfunction "+VIN_1") (pintype "power_in"))
      (node (ref "U8") (pin "1") (pinfunction "+VIN_1") (pintype "power_in"))
    )
    (net (code "4") (name "+Vout") (class "Default")
      (node (ref "C2") (pin "1") (pinfunction "1_1") (pintype "passive"))
      (node (ref "C5") (pin "1") (pinfunction "1_1") (pintype "passive"))
      (node (ref "C6") (pin "1") (pinfunction "1_1") (pintype "passive"))
      (node (ref "R2") (pin "2") (pinfunction "2_2") (pintype "passive"))
      (node (ref "R3") (pin "1") (pinfunction "1_1") (pintype "passive"))
      (node (ref "R4") (pin "1") (pinfunction "1_1") (pintype "passive"))
      (node (ref "R7") (pin "2") (pinfunction "2_2") (pintype "passive"))
      (node (ref "R9") (pin "1") (pinfunction "1_1") (pintype "passive"))
      (node (ref "TP4") (pin "1") (pinfunction "1_1") (pintype "passive"))
      (node (ref "U1") (pin "6") (pinfunction "OUT_6") (pintype "power_in"))
      (node (ref "U1") (pin "7") (pinfunction "OUT_7") (pintype "power_in"))
    )
    (net (code "5") (name "+Vout_Conn") (class "Default")
      (node (ref "J1") (pin "1") (pintype "power_in"))
      (node (ref "R5") (pin "2") (pinfunction "2_2") (pintype "passive"))
      (node (ref "S1") (pin "2") (pintype "power_in"))
    )
    (net (code "6") (name "/AC_L") (class "Default")
      (node (ref "J4") (pin "L") (pinfunction "L_L") (pintype "power_in"))
      (node (ref "U6") (pin "3") (pinfunction "AC/L_3") (pintype "power_in"))
    )
    (net (code "7") (name "/AC_N") (class "Default")
      (node (ref "J4") (pin "N") (pinfunction "N_N") (pintype "power_in"))
      (node (ref "U6") (pin "4") (pinfunction "AC/N_4") (pintype "power_in"))
    )
    (net (code "8") (name "/CLOCK") (class "Default")
      (node (ref "J3") (pin "5") (pinfunction "CLK_5") (pintype "bidirectional"))
      (node (ref "U5") (pin "27") (pinfunction "RB6/PGC_27") (pintype "bidirectional"))
    )
    (net (code "9") (name "/CONTRAST ADJ") (class "Default")
      (node (ref "LCD1") (pin "3") (pinfunction "V0_3") (pintype "power_in"))
      (node (ref "P3") (pin "2") (pintype "passive"))
    )
    (net (code "10") (name "/CURRENT_LIMIT_ADC") (class "Default")
      (node (ref "C12") (pin "1") (pinfunction "1_1") (pintype "passive"))
      (node (ref "R21") (pin "2") (pinfunction "2_2") (pintype "passive"))
      (node (ref "U5") (pin "4") (pinfunction "RA2/AN2/VREF-/CVREF_4") (pintype "bidirectional"))
    )
    (net (code "11") (name "/CURRENT_LIMIT_SENSE") (class "Default")
      (node (ref "R19") (pin "1") (pinfunction "1_1") (pintype "passive"))
      (node (ref "R20") (pin "2") (pinfunction "2_2") (pintype "passive"))
      (node (ref "R24") (pin "1") (pinfunction "1_1") (pintype "passive"))
      (node (ref "S2") (pin "3") (pinfunction "NO_3") (pintype "passive"))
    )
    (net (code "12") (name "/DATA") (class "Default")
      (node (ref "J3") (pin "4") (pinfunction "DATA_4") (pintype "bidirectional"))
      (node (ref "U5") (pin "28") (pinfunction "RB7/PGD_28") (pintype "bidirectional"))
    )
    (net (code "13") (name "/ILIM") (class "Default")
      (node (ref "R12") (pin "1") (pinfunction "1_1") (pintype "passive"))
      (node (ref "R13") (pin "2") (pinfunction "2_2") (pintype "passive"))
      (node (ref "R19") (pin "2") (pinfunction "2_2") (pintype "passive"))
      (node (ref "R6") (pin "2") (pinfunction "2_2") (pintype "passive"))
      (node (ref "S2") (pin "4") (pinfunction "NC_4") (pintype "passive"))
      (node (ref "U1") (pin "2") (pinfunction "IMON/ILIM_2") (pintype "input"))
      (node (ref "U3") (pin "7") (pinfunction "OUT1_7") (pintype "output"))
    )
    (net (code "14") (name "/LOAD_CURRENT_ADC") (class "Default")
      (node (ref "C8") (pin "1") (pinfunction "1_1") (pintype "passive"))
      (node (ref "R10") (pin "2") (pinfunction "2_2") (pintype "passive"))
      (node (ref "U5") (pin "3") (pinfunction "RA1/AN1_3") (pintype "bidirectional"))
    )
    (net (code "15") (name "/LOAD_VOLTAGE_ADC") (class "Default")
      (node (ref "C10") (pin "1") (pinfunction "1_1") (pintype "passive"))
      (node (ref "R18") (pin "2") (pinfunction "2_2") (pintype "passive"))
      (node (ref "U5") (pin "2") (pinfunction "RA0/AN0_2") (pintype "bidirectional"))
    )
    (net (code "16") (name "/LOAD_VOLTAGE_SENSE") (class "Default")
      (node (ref "R11") (pin "2") (pinfunction "2_2") (pintype "passive"))
      (node (ref "R7") (pin "1") (pinfunction "1_1") (pintype "passive"))
      (node (ref "U4") (pin "3") (pinfunction "+IN_3") (pintype "input"))
    )
    (net (code "17") (name "/LV ICSP") (class "Default")
      (node (ref "J3") (pin "6") (pinfunction "Low_voltage_ICSP_6") (pintype "bidirectional"))
      (node (ref "U5") (pin "24") (pinfunction "RB3/PGM_24") (pintype "bidirectional"))
    )
    (net (code "18") (name "/MCLRn") (class "Default")
      (node (ref "R22") (pin "1") (pinfunction "1_1") (pintype "passive"))
      (node (ref "S3") (pin "3") (pinfunction "3_3") (pintype "passive"))
      (node (ref "S3") (pin "4") (pinfunction "4_4") (pintype "passive"))
      (node (ref "U5") (pin "1") (pinfunction "~{MCLR}/VPP_1") (pintype "input"))
    )
    (net (code "19") (name "/Power_Good") (class "Default")
      (node (ref "LED1") (pin "K") (pinfunction "K_K") (pintype "passive"))
      (node (ref "U1") (pin "15") (pinfunction "PWRGD_15") (pintype "output"))
    )
    (net (code "20") (name "/RLIM") (class "Default")
      (node (ref "P1") (pin "2") (pintype "passive"))
      (node (ref "R23") (pin "1") (pinfunction "1_1") (pintype "passive"))
      (node (ref "R6") (pin "1") (pinfunction "1_1") (pintype "passive"))
    )
    (net (code "21") (name "/RSET") (class "Default")
      (node (ref "P2") (pin "2") (pintype "passive"))
      (node (ref "U1") (pin "5") (pinfunction "SET_5") (pintype "input"))
    )
    (net (code "22") (name "/SCL") (class "Default")
      (node (ref "R16") (pin "2") (pinfunction "2_2") (pintype "passive"))
      (node (ref "U3") (pin "2") (pinfunction "SDL_2") (pintype "bidirectional"))
      (node (ref "U5") (pin "14") (pinfunction "RC3/SCK/SCL_14") (pintype "bidirectional"))
    )
    (net (code "23") (name "/SDA") (class "Default")
      (node (ref "R17") (pin "2") (pinfunction "2_2") (pintype "passive"))
      (node (ref "U3") (pin "1") (pinfunction "SDA_1") (pintype "bidirectional"))
      (node (ref "U5") (pin "15") (pinfunction "RC4/SDI/SDA_15") (pintype "bidirectional"))
    )
    (net (code "24") (name "/TEMP_ADC") (class "Default")
      (node (ref "R26") (pin "1") (pinfunction "1_1") (pintype "passive"))
      (node (ref "U1") (pin "13") (pinfunction "TEMP_13") (pintype "output"))
    )
    (net (code "25") (name "EARTH_GND") (class "Default")
      (node (ref "H4") (pin "1") (pinfunction "1_1") (pintype "passive"))
      (node (ref "J4") (pin "GND") (pinfunction "GND_GND") (pintype "power_in"))
    )
    (net (code "26") (name "GND") (class "Default")
      (node (ref "C1") (pin "2") (pinfunction "2_2") (pintype "passive"))
      (node (ref "C10") (pin "2") (pinfunction "2_2") (pintype "passive"))
      (node (ref "C11") (pin "1") (pinfunction "1_1") (pintype "passive"))
      (node (ref "C12") (pin "2") (pinfunction "2_2") (pintype "passive"))
      (node (ref "C13") (pin "2") (pinfunction "2_2") (pintype "passive"))
      (node (ref "C14") (pin "2") (pinfunction "2_2") (pintype "passive"))
      (node (ref "C15") (pin "2") (pinfunction "2_2") (pintype "passive"))
      (node (ref "C16") (pin "2") (pinfunction "2_2") (pintype "passive"))
      (node (ref "C17") (pin "2") (pinfunction "2_2") (pintype "passive"))
      (node (ref "C18") (pin "2") (pinfunction "2_2") (pintype "passive"))
      (node (ref "C19") (pin "2") (pinfunction "2_2") (pintype "passive"))
      (node (ref "C2") (pin "2") (pinfunction "2_2") (pintype "passive"))
      (node (ref "C3") (pin "2") (pinfunction "2_2") (pintype "passive"))
      (node (ref "C4") (pin "2") (pinfunction "2_2") (pintype "passive"))
      (node (ref "C5") (pin "2") (pinfunction "2_2") (pintype "passive"))
      (node (ref "C6") (pin "2") (pinfunction "2_2") (pintype "passive"))
      (node (ref "C7") (pin "2") (pinfunction "2_2") (pintype "passive"))
      (node (ref "C8") (pin "2") (pinfunction "2_2") (pintype "passive"))
      (node (ref "C9") (pin "1") (pinfunction "1_1") (pintype "passive"))
      (node (ref "H1") (pin "1") (pinfunction "1_1") (pintype "passive"))
      (node (ref "H2") (pin "1") (pinfunction "1_1") (pintype "passive"))
      (node (ref "H3") (pin "1") (pinfunction "1_1") (pintype "passive"))
      (node (ref "J2") (pin "1") (pintype "power_in"))
      (node (ref "J3") (pin "3") (pinfunction "GND_3") (pintype "power_in"))
      (node (ref "J5") (pin "4") (pinfunction "GND_4") (pintype "power_in"))
      (node (ref "J5") (pin "8") (pinfunction "GND_8") (pintype "power_in"))
      (node (ref "J5") (pin "M1") (pinfunction "M1_M1") (pintype "passive"))
      (node (ref "J5") (pin "M2") (pinfunction "M2_M2") (pintype "passive"))
      (node (ref "J5") (pin "M3") (pinfunction "M3_M3") (pintype "passive"))
      (node (ref "J5") (pin "M4") (pinfunction "M4_M4") (pintype "passive"))
      (node (ref "J8") (pin "1") (pintype "power_in"))
      (node (ref "J9") (pin "1") (pintype "power_in"))
      (node (ref "LCD1") (pin "1") (pinfunction "VSS/GND_1") (pintype "power_in"))
      (node (ref "LCD1") (pin "16") (pinfunction "LED-_16") (pintype "power_in"))
      (node (ref "LCD1") (pin "5") (pinfunction "RW_5") (pintype "input"))
      (node (ref "LED2") (pin "K") (pinfunction "K_K") (pintype "passive"))
      (node (ref "LED3") (pin "K") (pinfunction "K_K") (pintype "passive"))
      (node (ref "LED4") (pin "K") (pinfunction "K_K") (pintype "passive"))
      (node (ref "P1") (pin "M1") (pintype "power_in"))
      (node (ref "P1") (pin "M2") (pintype "power_in"))
      (node (ref "P2") (pin "M1") (pintype "power_in"))
      (node (ref "P2") (pin "M2") (pintype "power_in"))
      (node (ref "P3") (pin "3") (pintype "passive"))
      (node (ref "P3") (pin "M1") (pintype "power_in"))
      (node (ref "P3") (pin "M2") (pintype "power_in"))
      (node (ref "R1") (pin "2") (pinfunction "2_2") (pintype "passive"))
      (node (ref "R11") (pin "1") (pinfunction "1_1") (pintype "passive"))
      (node (ref "R14") (pin "1") (pinfunction "1_1") (pintype "passive"))
      (node (ref "R15") (pin "1") (pinfunction "1_1") (pintype "passive"))
      (node (ref "R8") (pin "1") (pinfunction "1_1") (pintype "passive"))
      (node (ref "S2") (pin "M1") (pintype "power_in"))
      (node (ref "S2") (pin "M2") (pintype "power_in"))
      (node (ref "S3") (pin "1") (pinfunction "1_1") (pintype "passive"))
      (node (ref "S3") (pin "2") (pinfunction "2_2") (pintype "passive"))
      (node (ref "TP1") (pin "1") (pinfunction "1_1") (pintype "passive"))
      (node (ref "TP2") (pin "1") (pinfunction "1_1") (pintype "passive"))
      (node (ref "U1") (pin "1") (pinfunction "GND_1") (pintype "power_in"))
      (node (ref "U1") (pin "16") (pinfunction "GND_16") (pintype "power_in"))
      (node (ref "U1") (pin "17") (pinfunction "PGND_17") (pintype "power_in"))
      (node (ref "U1") (pin "8") (pinfunction "GND_8") (pintype "power_in"))
      (node (ref "U1") (pin "9") (pinfunction "GND_9") (pintype "power_in"))
      (node (ref "U2") (pin "1") (pinfunction "REF_1") (pintype "power_in"))
      (node (ref "U2") (pin "2") (pinfunction "GND_2") (pintype "power_in"))
      (node (ref "U3") (pin "4") (pinfunction "GND_4") (pintype "power_in"))
      (node (ref "U4") (pin "4") (pinfunction "V-_4") (pintype "power_in"))
      (node (ref "U5") (pin "19") (pinfunction "VSS_19") (pintype "power_in"))
      (node (ref "U5") (pin "8") (pinfunction "VSS_8") (pintype "power_in"))
      (node (ref "U6") (pin "2") (pinfunction "-V_2") (pintype "power_in"))
      (node (ref "U7") (pin "2") (pinfunction "GND_2") (pintype "power_in"))
      (node (ref "U8") (pin "2") (pinfunction "GND_2") (pintype "power_in"))
      (node (ref "X1") (pin "2") (pintype "passive"))
    )
    (net (code "27") (name "Net-(C9-Pad2)") (class "Default")
      (node (ref "C9") (pin "2") (pinfunction "2_2") (pintype "passive"))
      (node (ref "R13") (pin "1") (pinfunction "1_1") (pintype "passive"))
    )
    (net (code "28") (name "Net-(J5-D+-Pad3)") (class "Default")
      (node (ref "J5") (pin "3") (pinfunction "D+_3") (pintype "bidirectional"))
      (node (ref "R29") (pin "1") (pinfunction "1_1") (pintype "passive"))
    )
    (net (code "29") (name "Net-(J5-D+-Pad7)") (class "Default")
      (node (ref "J5") (pin "7") (pinfunction "D+_7") (pintype "bidirectional"))
      (node (ref "R30") (pin "1") (pinfunction "1_1") (pintype "passive"))
    )
    (net (code "30") (name "Net-(J5-D--Pad2)") (class "Default")
      (node (ref "J5") (pin "2") (pinfunction "D-_2") (pintype "bidirectional"))
      (node (ref "R29") (pin "2") (pinfunction "2_2") (pintype "passive"))
    )
    (net (code "31") (name "Net-(J5-D--Pad6)") (class "Default")
      (node (ref "J5") (pin "6") (pinfunction "D-_6") (pintype "bidirectional"))
      (node (ref "R30") (pin "2") (pinfunction "2_2") (pintype "passive"))
    )
    (net (code "32") (name "Net-(LCD1-DB4)") (class "Default")
      (node (ref "LCD1") (pin "11") (pinfunction "DB4_11") (pintype "bidirectional"))
      (node (ref "U5") (pin "13") (pinfunction "RC2/CCP1_13") (pintype "bidirectional"))
    )
    (net (code "33") (name "Net-(LCD1-DB5)") (class "Default")
      (node (ref "LCD1") (pin "12") (pinfunction "DB5_12") (pintype "bidirectional"))
      (node (ref "U5") (pin "16") (pinfunction "RC5/SDO_16") (pintype "bidirectional"))
    )
    (net (code "34") (name "Net-(LCD1-DB6)") (class "Default")
      (node (ref "LCD1") (pin "13") (pinfunction "DB6_13") (pintype "bidirectional"))
      (node (ref "U5") (pin "17") (pinfunction "RC6/TX/CK_17") (pintype "bidirectional"))
    )
    (net (code "35") (name "Net-(LCD1-DB7)") (class "Default")
      (node (ref "LCD1") (pin "14") (pinfunction "DB7_14") (pintype "bidirectional"))
      (node (ref "U5") (pin "18") (pinfunction "RC7/RX/DT_18") (pintype "bidirectional"))
    )
    (net (code "36") (name "Net-(LCD1-EN)") (class "Default")
      (node (ref "LCD1") (pin "6") (pinfunction "EN_6") (pintype "input"))
      (node (ref "U5") (pin "12") (pinfunction "RC1/T1OSI/CCP2_12") (pintype "bidirectional"))
    )
    (net (code "37") (name "Net-(LCD1-RS)") (class "Default")
      (node (ref "LCD1") (pin "4") (pinfunction "RS_4") (pintype "bidirectional"))
      (node (ref "U5") (pin "11") (pinfunction "RC0/T1OSO/T1CKI_11") (pintype "bidirectional"))
    )
    (net (code "38") (name "Net-(LED1-PadA)") (class "Default")
      (node (ref "LED1") (pin "A") (pinfunction "A_A") (pintype "passive"))
      (node (ref "R5") (pin "1") (pinfunction "1_1") (pintype "passive"))
    )
    (net (code "39") (name "Net-(LED2-PadA)") (class "Default")
      (node (ref "LED2") (pin "A") (pinfunction "A_A") (pintype "passive"))
      (node (ref "R25") (pin "1") (pinfunction "1_1") (pintype "passive"))
    )
    (net (code "40") (name "Net-(LED3-PadA)") (class "Default")
      (node (ref "LED3") (pin "A") (pinfunction "A_A") (pintype "passive"))
      (node (ref "R27") (pin "1") (pinfunction "1_1") (pintype "passive"))
    )
    (net (code "41") (name "Net-(LED4-PadA)") (class "Default")
      (node (ref "LED4") (pin "A") (pinfunction "A_A") (pintype "passive"))
      (node (ref "R28") (pin "1") (pinfunction "1_1") (pintype "passive"))
    )
    (net (code "42") (name "Net-(P1-Pad1)") (class "Default")
      (node (ref "P1") (pin "1") (pintype "passive"))
      (node (ref "R1") (pin "1") (pinfunction "1_1") (pintype "passive"))
    )
    (net (code "43") (name "Net-(P1-Pad3)") (class "Default")
      (node (ref "P1") (pin "3") (pintype "passive"))
      (node (ref "R8") (pin "2") (pinfunction "2_2") (pintype "passive"))
    )
    (net (code "44") (name "Net-(P2-Pad1)") (class "Default")
      (node (ref "P2") (pin "1") (pintype "passive"))
      (node (ref "R2") (pin "1") (pinfunction "1_1") (pintype "passive"))
    )
    (net (code "45") (name "Net-(P2-Pad3)") (class "Default")
      (node (ref "P2") (pin "3") (pintype "passive"))
      (node (ref "R9") (pin "2") (pinfunction "2_2") (pintype "passive"))
    )
    (net (code "46") (name "Net-(R3-Pad2)") (class "Default")
      (node (ref "R3") (pin "2") (pinfunction "2_2") (pintype "passive"))
      (node (ref "S1") (pin "1") (pintype "power_in"))
    )
    (net (code "47") (name "Net-(S2-COMM)") (class "Default")
      (node (ref "R23") (pin "2") (pinfunction "2_2") (pintype "passive"))
      (node (ref "S2") (pin "1") (pinfunction "COMM_1") (pintype "passive"))
    )
    (net (code "48") (name "Net-(U1-RPWRGD)") (class "Default")
      (node (ref "R4") (pin "2") (pinfunction "2_2") (pintype "passive"))
      (node (ref "U1") (pin "4") (pinfunction "RPWRGD_4") (pintype "input"))
    )
    (net (code "49") (name "Net-(U2-IN+)") (class "Default")
      (node (ref "R3") (pin "3") (pinfunction "3_3") (pintype "passive"))
      (node (ref "U2") (pin "4") (pinfunction "IN+_4") (pintype "input"))
    )
    (net (code "50") (name "Net-(U2-IN-)") (class "Default")
      (node (ref "R3") (pin "4") (pinfunction "4_4") (pintype "passive"))
      (node (ref "U2") (pin "5") (pinfunction "IN-_5") (pintype "input"))
    )
    (net (code "51") (name "Net-(U2-OUT)") (class "Default")
      (node (ref "R10") (pin "1") (pinfunction "1_1") (pintype "passive"))
      (node (ref "U2") (pin "6") (pinfunction "OUT_6") (pintype "output"))
    )
    (net (code "52") (name "Net-(U3-FS0)") (class "Default")
      (node (ref "R14") (pin "2") (pinfunction "2_2") (pintype "passive"))
      (node (ref "U3") (pin "5") (pinfunction "FS0_5") (pintype "input"))
    )
    (net (code "53") (name "Net-(U3-FS1)") (class "Default")
      (node (ref "R15") (pin "2") (pinfunction "2_2") (pintype "passive"))
      (node (ref "U3") (pin "3") (pinfunction "FS1_3") (pintype "input"))
    )
    (net (code "54") (name "Net-(U3-OUT0)") (class "Default")
      (node (ref "R12") (pin "2") (pinfunction "2_2") (pintype "passive"))
      (node (ref "U3") (pin "6") (pinfunction "OUT0_6") (pintype "output"))
    )
    (net (code "55") (name "Net-(U4A--IN)") (class "Default")
      (node (ref "R18") (pin "1") (pinfunction "1_1") (pintype "passive"))
      (node (ref "U4") (pin "1") (pinfunction "OUT_1") (pintype "output"))
      (node (ref "U4") (pin "2") (pinfunction "-IN_2") (pintype "input"))
    )
    (net (code "56") (name "Net-(U4B-+IN)") (class "Default")
      (node (ref "C11") (pin "2") (pinfunction "2_2") (pintype "passive"))
      (node (ref "R20") (pin "1") (pinfunction "1_1") (pintype "passive"))
      (node (ref "U4") (pin "5") (pinfunction "+IN_5") (pintype "input"))
    )
    (net (code "57") (name "Net-(U4B--IN)") (class "Default")
      (node (ref "R21") (pin "1") (pinfunction "1_1") (pintype "passive"))
      (node (ref "U4") (pin "6") (pinfunction "-IN_6") (pintype "input"))
      (node (ref "U4") (pin "7") (pinfunction "OUT_7") (pintype "output"))
    )
    (net (code "58") (name "Net-(U5-OSC1{slash}CLKI)") (class "Default")
      (node (ref "U5") (pin "9") (pinfunction "OSC1/CLKI_9") (pintype "input"))
      (node (ref "X1") (pin "1") (pintype "passive"))
    )
    (net (code "59") (name "Net-(U5-OSC2{slash}CLKO)") (class "Default")
      (node (ref "U5") (pin "10") (pinfunction "OSC2/CLKO_10") (pintype "output"))
      (node (ref "X1") (pin "3") (pintype "passive"))
    )
    (net (code "60") (name "Net-(U5-RA3{slash}AN3{slash}VREF+)") (class "Default")
      (node (ref "C15") (pin "1") (pinfunction "1_1") (pintype "passive"))
      (node (ref "R26") (pin "2") (pinfunction "2_2") (pintype "passive"))
      (node (ref "U5") (pin "5") (pinfunction "RA3/AN3/VREF+_5") (pintype "bidirectional"))
    )
    (net (code "61") (name "unconnected-(J3-~{MCLR}-Pad1)") (class "Default")
      (node (ref "J3") (pin "1") (pinfunction "~{MCLR}_1") (pintype "power_in+no_connect"))
    )
    (net (code "62") (name "unconnected-(LCD1-DB0-Pad7)") (class "Default")
      (node (ref "LCD1") (pin "7") (pinfunction "DB0_7") (pintype "bidirectional+no_connect"))
    )
    (net (code "63") (name "unconnected-(LCD1-DB1-Pad8)") (class "Default")
      (node (ref "LCD1") (pin "8") (pinfunction "DB1_8") (pintype "bidirectional+no_connect"))
    )
    (net (code "64") (name "unconnected-(LCD1-DB2-Pad9)") (class "Default")
      (node (ref "LCD1") (pin "9") (pinfunction "DB2_9") (pintype "bidirectional+no_connect"))
    )
    (net (code "65") (name "unconnected-(LCD1-DB3-Pad10)") (class "Default")
      (node (ref "LCD1") (pin "10") (pinfunction "DB3_10") (pintype "bidirectional+no_connect"))
    )
    (net (code "66") (name "unconnected-(U1-CDC-Pad3)") (class "Default")
      (node (ref "U1") (pin "3") (pinfunction "CDC_3") (pintype "output+no_connect"))
    )
    (net (code "67") (name "unconnected-(U1-TRACK-Pad14)") (class "Default")
      (node (ref "U1") (pin "14") (pinfunction "TRACK_14") (pintype "input+no_connect"))
    )
    (net (code "68") (name "unconnected-(U5-RA4{slash}T0CKI{slash}C1OUT-Pad6)") (class "Default")
      (node (ref "U5") (pin "6") (pinfunction "RA4/T0CKI/C1OUT_6") (pintype "bidirectional"))
    )
    (net (code "69") (name "unconnected-(U5-RA5{slash}AN4{slash}~{SS}{slash}C2OUT-Pad7)") (class "Default")
      (node (ref "U5") (pin "7") (pinfunction "RA5/AN4/~{SS}/C2OUT_7") (pintype "bidirectional"))
    )
    (net (code "70") (name "unconnected-(U5-RB0{slash}INT-Pad21)") (class "Default")
      (node (ref "U5") (pin "21") (pinfunction "RB0/INT_21") (pintype "bidirectional+no_connect"))
    )
    (net (code "71") (name "unconnected-(U5-RB1-Pad22)") (class "Default")
      (node (ref "U5") (pin "22") (pinfunction "RB1_22") (pintype "bidirectional+no_connect"))
    )
    (net (code "72") (name "unconnected-(U5-RB2-Pad23)") (class "Default")
      (node (ref "U5") (pin "23") (pinfunction "RB2_23") (pintype "bidirectional+no_connect"))
    )
    (net (code "73") (name "unconnected-(U5-RB4-Pad25)") (class "Default")
      (node (ref "U5") (pin "25") (pinfunction "RB4_25") (pintype "bidirectional+no_connect"))
    )
    (net (code "74") (name "unconnected-(U5-RB5-Pad26)") (class "Default")
      (node (ref "U5") (pin "26") (pinfunction "RB5_26") (pintype "bidirectional+no_connect"))
    )
  )
)
